# ProProject_Air001_2024-07-03.net
KiCad netlist of a schematic drawn in EasyEDA Pro
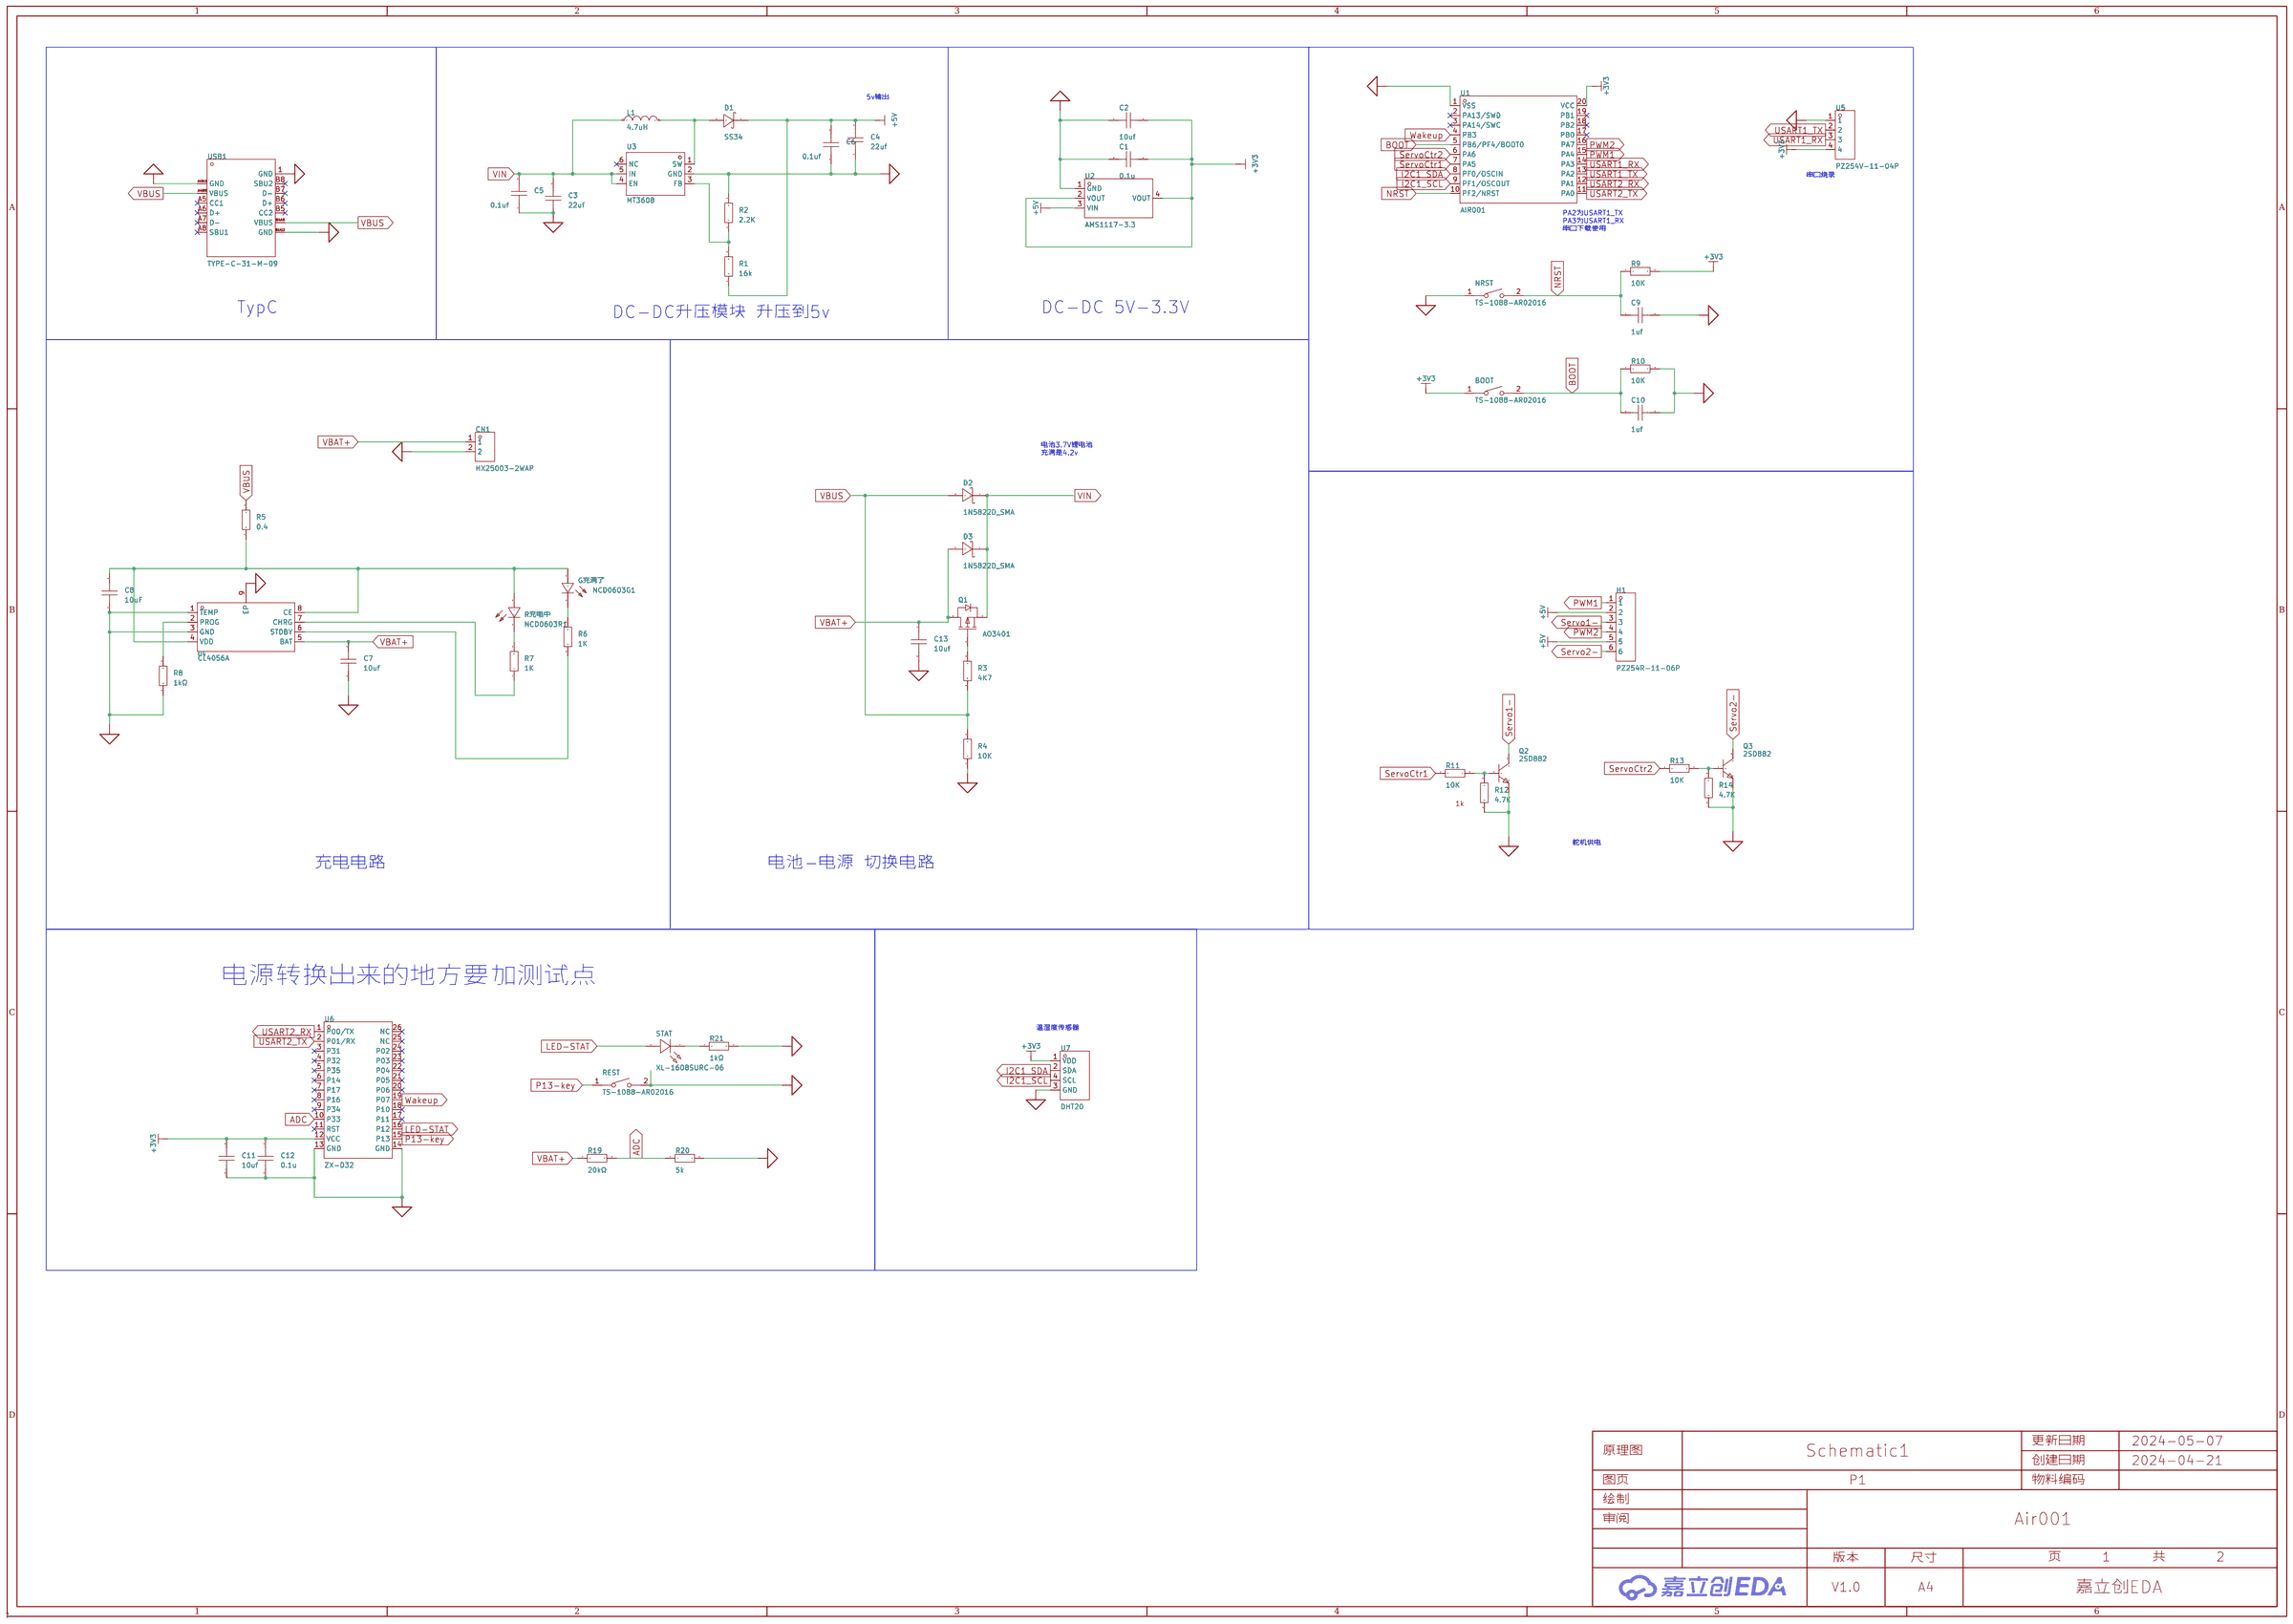
[diagram p0: schematic sheet]

(export (version "E")
  (design (tool "Eeschema 10.0.6"))
  (components
    (comp (ref "BOOT")
      (value "TS-1088-AR02016")
      (footprint "easyedapro:SW-SMD_L3.9-W3.0-P4.45")
      (fields (field (name "Manufacturer") "XUNPU(讯普)"))
      (libsource (lib "easyedapro") (part "TS-1088-AR02016"))
    )
    (comp (ref "C1")
      (value "0.1u")
      (footprint "easyedapro:C0603")
      (libsource (lib "easyedapro") (part "CapAcitance"))
    )
    (comp (ref "C2")
      (value "10uf")
      (footprint "easyedapro:C0603")
      (libsource (lib "easyedapro") (part "CapAcitance"))
    )
    (comp (ref "C3")
      (value "22uf")
      (footprint "easyedapro:C0603")
      (libsource (lib "easyedapro") (part "CapAcitance"))
    )
    (comp (ref "C4")
      (value "22uf")
      (footprint "easyedapro:C0603")
      (libsource (lib "easyedapro") (part "CapAcitance"))
    )
    (comp (ref "C5")
      (value "0.1uf")
      (footprint "easyedapro:C0603")
      (libsource (lib "easyedapro") (part "CapAcitance"))
    )
    (comp (ref "C6")
      (value "0.1uf")
      (footprint "easyedapro:C0603")
      (libsource (lib "easyedapro") (part "CapAcitance"))
    )
    (comp (ref "C7")
      (value "10uf")
      (footprint "easyedapro:C0603")
      (libsource (lib "easyedapro") (part "CapAcitance"))
    )
    (comp (ref "C8")
      (value "10uF")
      (footprint "easyedapro:C0603")
      (fields
        (field (name "Manufacturer Part") "CL10A106MA8NRNC")
        (field (name "Manufacturer") "SAMSUNG(三星)")
      )
      (libsource (lib "easyedapro") (part "CapAcitance"))
    )
    (comp (ref "C9")
      (value "1uf")
      (footprint "easyedapro:C0603")
      (libsource (lib "easyedapro") (part "CapAcitance"))
    )
    (comp (ref "C10")
      (value "1uf")
      (footprint "easyedapro:C0603")
      (libsource (lib "easyedapro") (part "CapAcitance"))
    )
    (comp (ref "C11")
      (value "10uf")
      (footprint "easyedapro:C0603")
      (libsource (lib "easyedapro") (part "CapAcitance"))
    )
    (comp (ref "C12")
      (value "0.1u")
      (footprint "easyedapro:C0603")
      (libsource (lib "easyedapro") (part "CapAcitance"))
    )
    (comp (ref "C13")
      (value "10uf")
      (footprint "easyedapro:C0603")
      (libsource (lib "easyedapro") (part "CapAcitance"))
    )
    (comp (ref "CN1")
      (value "HX25003-2WAP")
      (footprint "easyedapro:CONN-TH_2P-P2.50_HX25003-2WAP")
      (description "插针结构:1x2P;间距:2.5mm;安装方式:弯插;参考系列:XH;总PIN数:2P;排数:1;每排PIN数:2;行距:-;额定电流:-;工作温度范围:-;")
      (fields (field (name "Manufacturer") "HX(红星)"))
      (libsource (lib "easyedapro") (part "HX25003-2WAP"))
    )
    (comp (ref "D1")
      (value "SS34")
      (footprint "easyedapro:SMA_L4.3-W2.6-LS5.2-RD")
      (description "二极管配置:独立式;正向压降(Vf):550mV@3A;直流反向耐压(Vr):40V;平均整流电流(Io):3A;")
      (fields (field (name "Manufacturer") "MDD"))
      (libsource (lib "easyedapro") (part "SS34_C8678"))
    )
    (comp (ref "D2")
      (value "1N5822D_SMA")
      (footprint "easyedapro:SMA_L4.3-W2.6-LS5.2-RD")
      (description "二极管配置:独立式;正向压降(Vf):550mV@3A;直流反向耐压(Vr):40V;平均整流电流(Io):3A;")
      (fields (field (name "Manufacturer") "MDD"))
      (libsource (lib "easyedapro") (part "SS34_C8678"))
    )
    (comp (ref "D3")
      (value "1N5822D_SMA")
      (footprint "easyedapro:SMA_L4.3-W2.6-LS5.2-RD")
      (description "二极管配置:独立式;正向压降(Vf):550mV@3A;直流反向耐压(Vr):40V;平均整流电流(Io):3A;")
      (fields (field (name "Manufacturer") "MDD"))
      (libsource (lib "easyedapro") (part "SS34_C8678"))
    )
    (comp (ref "G充满了")
      (value "NCD0603G1")
      (footprint "easyedapro:LED0603-RD")
      (fields (field (name "Manufacturer") "国星光电"))
      (libsource (lib "easyedapro") (part "FC-D1608UGK-520D10"))
    )
    (comp (ref "H1")
      (value "PZ254R-11-06P")
      (footprint "easyedapro:HDR-TH_6P-P2.54-H-M-W10.4")
      (fields (field (name "Manufacturer") "XFCN(兴飞)"))
      (libsource (lib "easyedapro") (part "PZ254R-11-06P"))
    )
    (comp (ref "L1")
      (value "4.7uH")
      (fields (field (name "Manufacturer Part") "YSPI1050-4R7M") (field (name "Manufacturer") "YJYCOIN(益嘉源)"))
      (libsource (lib "easyedapro") (part "SDFL1608S100KTF"))
    )
    (comp (ref "NRST")
      (value "TS-1088-AR02016")
      (footprint "easyedapro:SW-SMD_L3.9-W3.0-P4.45")
      (fields (field (name "Manufacturer") "XUNPU(讯普)"))
      (libsource (lib "easyedapro") (part "TS-1088-AR02016"))
    )
    (comp (ref "Q1")
      (value "AO3401")
      (footprint "easyedapro:SOT-23-3_L2.9-W1.6-P1.90-LS2.8-BR")
      (fields (field (name "Manufacturer") "LGE(鲁光)"))
      (libsource (lib "easyedapro") (part "AO3401_C688915"))
    )
    (comp (ref "Q2")
      (value "2SD882")
      (footprint "easyedapro:SOT-89-3_L4.5-W2.5-P1.50-LS4.1-BR")
      (description "晶体管类型:NPN;集电极电流(Ic):3A;集射极击穿电压(Vceo):30V;功率(Pd):500mW;")
      (fields (field (name "Manufacturer") "FUXINSEMI(富芯森美)"))
      (libsource (lib "easyedapro") (part "2SD882_C842818"))
    )
    (comp (ref "Q3")
      (value "2SD882")
      (footprint "easyedapro:SOT-89-3_L4.5-W2.5-P1.50-LS4.1-BR")
      (description "晶体管类型:NPN;集电极电流(Ic):3A;集射极击穿电压(Vceo):30V;功率(Pd):500mW;")
      (fields (field (name "Manufacturer") "FUXINSEMI(富芯森美)"))
      (libsource (lib "easyedapro") (part "2SD882_C842818"))
    )
    (comp (ref "R1") (value "16k") (footprint "easyedapro:R0603") (libsource (lib "easyedapro") (part "电阻")))
    (comp (ref "R2") (value "2.2K") (footprint "easyedapro:R0603") (libsource (lib "easyedapro") (part "电阻")))
    (comp (ref "R3") (value "4K7") (footprint "easyedapro:R0603") (libsource (lib "easyedapro") (part "电阻")))
    (comp (ref "R4") (value "10K") (footprint "easyedapro:R0603") (libsource (lib "easyedapro") (part "电阻")))
    (comp (ref "R5") (value "0.4") (footprint "easyedapro:R0603") (libsource (lib "easyedapro") (part "电阻")))
    (comp (ref "R6") (value "1K") (footprint "easyedapro:R0603") (libsource (lib "easyedapro") (part "电阻")))
    (comp (ref "R7") (value "1K") (footprint "easyedapro:R0603") (libsource (lib "easyedapro") (part "电阻")))
    (comp (ref "R8")
      (value "1kΩ")
      (footprint "easyedapro:R0603")
      (fields (field (name "Manufacturer Part") "RC0603FR-071KL") (field (name "Manufacturer") "YAGEO(国巨)"))
      (libsource (lib "easyedapro") (part "电阻"))
    )
    (comp (ref "R9") (value "10K") (footprint "easyedapro:R0603") (libsource (lib "easyedapro") (part "电阻")))
    (comp (ref "R10") (value "10K") (footprint "easyedapro:R0603") (libsource (lib "easyedapro") (part "电阻")))
    (comp (ref "R11") (value "10K") (footprint "easyedapro:R0603") (libsource (lib "easyedapro") (part "电阻")))
    (comp (ref "R12")
      (value "4.7K")
      (footprint "easyedapro:R0603")
      (libsource (lib "easyedapro") (part "电阻"))
    )
    (comp (ref "R13") (value "10K") (footprint "easyedapro:R0603") (libsource (lib "easyedapro") (part "电阻")))
    (comp (ref "R14")
      (value "4.7K")
      (footprint "easyedapro:R0603")
      (libsource (lib "easyedapro") (part "电阻"))
    )
    (comp (ref "R19")
      (value "20kΩ")
      (fields
        (field (name "Manufacturer Part") "0603WAF1002T5E")
        (field (name "Manufacturer") "UNI-ROYAL(厚声)")
      )
      (libsource (lib "easyedapro") (part "电阻"))
    )
    (comp (ref "R20")
      (value "5k")
      (fields
        (field (name "Manufacturer Part") "0603WAF2701T5E")
        (field (name "Manufacturer") "UNI-ROYAL(厚声)")
      )
      (libsource (lib "easyedapro") (part "电阻"))
    )
    (comp (ref "R21")
      (value "1kΩ")
      (fields (field (name "Manufacturer Part") "RC0603FR-071KL") (field (name "Manufacturer") "YAGEO(国巨)"))
      (libsource (lib "easyedapro") (part "电阻"))
    )
    (comp (ref "REST")
      (value "TS-1088-AR02016")
      (footprint "easyedapro:SW-SMD_L3.9-W3.0-P4.45")
      (fields (field (name "Manufacturer") "XUNPU(讯普)"))
      (libsource (lib "easyedapro") (part "TS-1088-AR02016"))
    )
    (comp (ref "R充电中")
      (value "NCD0603R1")
      (footprint "easyedapro:LED0603-RD_RED")
      (fields (field (name "Manufacturer") "国星光电"))
      (libsource (lib "easyedapro") (part "FC-DA1608HRK-620D"))
    )
    (comp (ref "STAT")
      (value "XL-1608SURC-06")
      (footprint "easyedapro:LED0603-RD_RED")
      (description "发光颜色:红色;功率:55mW;正向电流:25mA;主波长:617nm~621nm;透镜颜色:无色透明透镜;色温:-;发光角度:120°;载带方式:正贴;工作温度:-30°C~+85°C;")
      (fields (field (name "Manufacturer") "XINGLIGHT(成兴光)"))
      (libsource (lib "easyedapro") (part "XL-1608SURC-06"))
    )
    (comp (ref "U1")
      (value "AIR001")
      (footprint "easyedapro:TSSOP-20_L6.5-W4.4-P0.65-LS6.4-BL")
      (libsource (lib "easyedapro") (part "AIR001"))
    )
    (comp (ref "U2")
      (value "AMS1117-3.3")
      (footprint "easyedapro:SOT-223-3_L6.5-W3.4-P2.30-LS7.0-BR")
      (description "输出类型:固定;最大输入电压:-;输出电压:3.3V;最大输出电流:1A;电源纹波抑制比(PSRR):72dB@(120Hz);输出极性:正极;")
      (fields (field (name "Manufacturer") "AMS"))
      (libsource (lib "easyedapro") (part "AMS1117-3.3"))
    )
    (comp (ref "U3")
      (value "MT3608")
      (footprint "easyedapro:SOT-23-6_L2.9-W1.6-P0.95-LS2.8-BL")
      (description "功能类型:升压型;输入电压:2V~24V;输出电压:28V;输出电流(最大值):-;")
      (fields (field (name "Manufacturer") "西安航天民芯"))
      (libsource (lib "easyedapro") (part "MT3608"))
    )
    (comp (ref "U4")
      (value "CL4056A")
      (footprint "easyedapro:ESOP-8_L4.9-W3.9-P1.27-LS6.0-BL-EP")
      (fields (field (name "Manufacturer") "CHIPLINK(芯联)"))
      (libsource (lib "easyedapro") (part "CL4056"))
    )
    (comp (ref "U5")
      (value "PZ254V-11-04P")
      (footprint "easyedapro:HDR-TH_4P-P2.54-V-M-3")
      (fields (field (name "Manufacturer") "XFCN(兴飞)"))
      (libsource (lib "easyedapro") (part "SIP4-CON4排针"))
    )
    (comp (ref "U6")
      (value "ZX-D32")
      (footprint "easyedapro:WIFIM-SMD_26P-L26.7-W13.0-P1.50")
      (libsource (lib "easyedapro") (part "ZX-D32_C9900104345"))
    )
    (comp (ref "U7")
      (value "DHT20")
      (footprint "easyedapro:SENSOR-TH_DHT20")
      (fields (field (name "Manufacturer") "广州奥松"))
      (libsource (lib "easyedapro") (part "DHT20"))
    )
    (comp (ref "USB1")
      (value "TYPE-C-31-M-09")
      (footprint "easyedapro:USB-C-SMD_TYPE-C-31-M-09")
      (description "连接器类型:Type-C;标准:-;公母:母;端口数量:1;触点数量:16P;安装方式:卧贴;额定电流 - 电源:-;工作温度范围:-40°C~+80°C;")
      (fields (field (name "Manufacturer") "韩国韩荣"))
      (libsource (lib "easyedapro") (part "TYPE-C-31-M-09"))
    )
  )
  (nets
    (net (code "1") (name "+3V3") (class "Default")
      (node (ref "BOOT") (pin "1") (pinfunction "1_1") (pintype "unspecified"))
      (node (ref "C1") (pin "1") (pinfunction "1_1") (pintype "input"))
      (node (ref "C11") (pin "2") (pinfunction "2_2") (pintype "input"))
      (node (ref "C12") (pin "1") (pinfunction "1_1") (pintype "input"))
      (node (ref "C2") (pin "2") (pinfunction "2_2") (pintype "input"))
      (node (ref "R9") (pin "2") (pinfunction "2_2") (pintype "input"))
      (node (ref "U1") (pin "20") (pinfunction "VCC_20") (pintype "unspecified"))
      (node (ref "U2") (pin "2") (pinfunction "VOUT_2") (pintype "unspecified"))
      (node (ref "U2") (pin "4") (pinfunction "VOUT_4") (pintype "unspecified"))
      (node (ref "U5") (pin "4") (pinfunction "4_4") (pintype "unspecified"))
      (node (ref "U6") (pin "12") (pinfunction "VCC_12") (pintype "unspecified"))
      (node (ref "U7") (pin "1") (pinfunction "VDD_1") (pintype "unspecified"))
    )
    (net (code "2") (name "+5V") (class "Default")
      (node (ref "C4") (pin "2") (pinfunction "2_2") (pintype "input"))
      (node (ref "C6") (pin "2") (pinfunction "2_2") (pintype "input"))
      (node (ref "D1") (pin "1") (pinfunction "K_1") (pintype "unspecified"))
      (node (ref "H1") (pin "2") (pinfunction "2_2") (pintype "unspecified"))
      (node (ref "H1") (pin "5") (pinfunction "5_5") (pintype "unspecified"))
      (node (ref "R1") (pin "1") (pinfunction "1_1") (pintype "input"))
      (node (ref "U2") (pin "3") (pinfunction "VIN_3") (pintype "unspecified"))
    )
    (net (code "3") (name "ADC") (class "Default")
      (node (ref "R19") (pin "2") (pinfunction "2_2") (pintype "input"))
      (node (ref "R20") (pin "1") (pinfunction "1_1") (pintype "input"))
      (node (ref "U6") (pin "10") (pinfunction "P33_10") (pintype "unspecified"))
    )
    (net (code "4") (name "AGND") (class "Default")
      (node (ref "C1") (pin "2") (pinfunction "2_2") (pintype "input"))
      (node (ref "C10") (pin "2") (pinfunction "2_2") (pintype "input"))
      (node (ref "C11") (pin "1") (pinfunction "1_1") (pintype "input"))
      (node (ref "C12") (pin "2") (pinfunction "2_2") (pintype "input"))
      (node (ref "C13") (pin "2") (pinfunction "2_2") (pintype "input"))
      (node (ref "C2") (pin "1") (pinfunction "1_1") (pintype "input"))
      (node (ref "C3") (pin "1") (pinfunction "1_1") (pintype "input"))
      (node (ref "C4") (pin "1") (pinfunction "1_1") (pintype "input"))
      (node (ref "C5") (pin "1") (pinfunction "1_1") (pintype "input"))
      (node (ref "C6") (pin "1") (pinfunction "1_1") (pintype "input"))
      (node (ref "C7") (pin "2") (pinfunction "2_2") (pintype "input"))
      (node (ref "C8") (pin "1") (pinfunction "1_1") (pintype "input"))
      (node (ref "C9") (pin "2") (pinfunction "2_2") (pintype "input"))
      (node (ref "CN1") (pin "2") (pinfunction "2_2") (pintype "unspecified"))
      (node (ref "NRST") (pin "1") (pinfunction "1_1") (pintype "unspecified"))
      (node (ref "Q2") (pin "3") (pinfunction "E_3") (pintype "unspecified"))
      (node (ref "Q3") (pin "3") (pinfunction "E_3") (pintype "unspecified"))
      (node (ref "R10") (pin "2") (pinfunction "2_2") (pintype "input"))
      (node (ref "R12") (pin "1") (pinfunction "1_1") (pintype "input"))
      (node (ref "R14") (pin "1") (pinfunction "1_1") (pintype "input"))
      (node (ref "R2") (pin "2") (pinfunction "2_2") (pintype "input"))
      (node (ref "R20") (pin "2") (pinfunction "2_2") (pintype "input"))
      (node (ref "R21") (pin "2") (pinfunction "2_2") (pintype "input"))
      (node (ref "R4") (pin "1") (pinfunction "1_1") (pintype "input"))
      (node (ref "R8") (pin "1") (pinfunction "1_1") (pintype "input"))
      (node (ref "REST") (pin "2") (pinfunction "2_2") (pintype "unspecified"))
      (node (ref "U1") (pin "1") (pinfunction "VSS_1") (pintype "unspecified"))
      (node (ref "U2") (pin "1") (pinfunction "GND_1") (pintype "unspecified"))
      (node (ref "U3") (pin "2") (pinfunction "GND_2") (pintype "input"))
      (node (ref "U4") (pin "1") (pinfunction "TEMP_1") (pintype "input"))
      (node (ref "U4") (pin "3") (pinfunction "GND_3") (pintype "input"))
      (node (ref "U4") (pin "9") (pinfunction "EP_9") (pintype "input"))
      (node (ref "U5") (pin "1") (pinfunction "1_1") (pintype "unspecified"))
      (node (ref "U6") (pin "13") (pinfunction "GND_13") (pintype "unspecified"))
      (node (ref "U6") (pin "14") (pinfunction "GND_14") (pintype "unspecified"))
      (node (ref "U7") (pin "3") (pinfunction "GND_3") (pintype "unspecified"))
      (node (ref "USB1") (pin "1") (pinfunction "GND_1") (pintype "unspecified"))
      (node (ref "USB1") (pin "A1B12") (pinfunction "GND_A1B12") (pintype "unspecified"))
      (node (ref "USB1") (pin "B1A12") (pinfunction "GND_B1A12") (pintype "unspecified"))
    )
    (net (code "5") (name "BOOT") (class "Default")
      (node (ref "BOOT") (pin "2") (pinfunction "2_2") (pintype "unspecified"))
      (node (ref "C10") (pin "1") (pinfunction "1_1") (pintype "input"))
      (node (ref "R10") (pin "1") (pinfunction "1_1") (pintype "input"))
      (node (ref "U1") (pin "5") (pinfunction "PB6/PF4/BOOT0_5") (pintype "unspecified"))
    )
    (net (code "6") (name "I2C1_SCL") (class "Default")
      (node (ref "U1") (pin "9") (pinfunction "PF1/OSCOUT_9") (pintype "unspecified"))
      (node (ref "U7") (pin "4") (pinfunction "SCL_4") (pintype "unspecified"))
    )
    (net (code "7") (name "I2C1_SDA") (class "Default")
      (node (ref "U1") (pin "8") (pinfunction "PF0/OSCIN_8") (pintype "unspecified"))
      (node (ref "U7") (pin "2") (pinfunction "SDA_2") (pintype "unspecified"))
    )
    (net (code "8") (name "LED-STAT") (class "Default")
      (node (ref "STAT") (pin "2") (pinfunction "A_2") (pintype "unspecified"))
      (node (ref "U6") (pin "16") (pinfunction "P12_16") (pintype "unspecified"))
    )
    (net (code "9") (name "NRST") (class "Default")
      (node (ref "C9") (pin "1") (pinfunction "1_1") (pintype "input"))
      (node (ref "NRST") (pin "2") (pinfunction "2_2") (pintype "unspecified"))
      (node (ref "R9") (pin "1") (pinfunction "1_1") (pintype "input"))
      (node (ref "U1") (pin "10") (pinfunction "PF2/NRST_10") (pintype "unspecified"))
    )
    (net (code "10") (name "Net-(D1-A)") (class "Default")
      (node (ref "D1") (pin "2") (pinfunction "A_2") (pintype "unspecified"))
      (node (ref "L1") (pin "2") (pinfunction "2_2") (pintype "unspecified"))
      (node (ref "U3") (pin "1") (pinfunction "SW_1") (pintype "input"))
    )
    (net (code "11") (name "Net-(G充满了-A)") (class "Default")
      (node (ref "C8") (pin "2") (pinfunction "2_2") (pintype "input"))
      (node (ref "G充满了") (pin "2") (pinfunction "A_2") (pintype "input"))
      (node (ref "R5") (pin "1") (pinfunction "1_1") (pintype "input"))
      (node (ref "R充电中") (pin "2") (pinfunction "A_2") (pintype "input"))
      (node (ref "U4") (pin "4") (pinfunction "VDD_4") (pintype "input"))
      (node (ref "U4") (pin "8") (pinfunction "CE_8") (pintype "input"))
    )
    (net (code "12") (name "Net-(G充满了-K)") (class "Default")
      (node (ref "G充满了") (pin "1") (pinfunction "K_1") (pintype "input"))
      (node (ref "R6") (pin "2") (pinfunction "2_2") (pintype "input"))
    )
    (net (code "13") (name "Net-(Q1-G)") (class "Default")
      (node (ref "Q1") (pin "1") (pinfunction "G_1") (pintype "unspecified"))
      (node (ref "R3") (pin "2") (pinfunction "2_2") (pintype "input"))
    )
    (net (code "14") (name "Net-(Q2-B)") (class "Default")
      (node (ref "Q2") (pin "1") (pinfunction "B_1") (pintype "unspecified"))
      (node (ref "R11") (pin "2") (pinfunction "2_2") (pintype "input"))
      (node (ref "R12") (pin "2") (pinfunction "2_2") (pintype "input"))
    )
    (net (code "15") (name "Net-(Q3-B)") (class "Default")
      (node (ref "Q3") (pin "1") (pinfunction "B_1") (pintype "unspecified"))
      (node (ref "R13") (pin "2") (pinfunction "2_2") (pintype "input"))
      (node (ref "R14") (pin "2") (pinfunction "2_2") (pintype "input"))
    )
    (net (code "16") (name "Net-(R充电中-K)") (class "Default")
      (node (ref "R7") (pin "2") (pinfunction "2_2") (pintype "input"))
      (node (ref "R充电中") (pin "1") (pinfunction "K_1") (pintype "input"))
    )
    (net (code "17") (name "Net-(STAT-K)") (class "Default")
      (node (ref "R21") (pin "1") (pinfunction "1_1") (pintype "input"))
      (node (ref "STAT") (pin "1") (pinfunction "K_1") (pintype "unspecified"))
    )
    (net (code "18") (name "Net-(U3-FB)") (class "Default")
      (node (ref "R1") (pin "2") (pinfunction "2_2") (pintype "input"))
      (node (ref "R2") (pin "1") (pinfunction "1_1") (pintype "input"))
      (node (ref "U3") (pin "3") (pinfunction "FB_3") (pintype "input"))
    )
    (net (code "19") (name "Net-(U4-CHRG)") (class "Default")
      (node (ref "R7") (pin "1") (pinfunction "1_1") (pintype "input"))
      (node (ref "U4") (pin "7") (pinfunction "CHRG_7") (pintype "input"))
    )
    (net (code "20") (name "Net-(U4-PROG)") (class "Default")
      (node (ref "R8") (pin "2") (pinfunction "2_2") (pintype "input"))
      (node (ref "U4") (pin "2") (pinfunction "PROG_2") (pintype "input"))
    )
    (net (code "21") (name "Net-(U4-STDBY)") (class "Default")
      (node (ref "R6") (pin "1") (pinfunction "1_1") (pintype "input"))
      (node (ref "U4") (pin "6") (pinfunction "STDBY_6") (pintype "input"))
    )
    (net (code "22") (name "P13-key") (class "Default")
      (node (ref "REST") (pin "1") (pinfunction "1_1") (pintype "unspecified"))
      (node (ref "U6") (pin "15") (pinfunction "P13_15") (pintype "unspecified"))
    )
    (net (code "23") (name "PWM1") (class "Default")
      (node (ref "H1") (pin "1") (pinfunction "1_1") (pintype "unspecified"))
      (node (ref "U1") (pin "15") (pinfunction "PA4_15") (pintype "unspecified"))
    )
    (net (code "24") (name "PWM2") (class "Default")
      (node (ref "H1") (pin "4") (pinfunction "4_4") (pintype "unspecified"))
      (node (ref "U1") (pin "16") (pinfunction "PA7_16") (pintype "unspecified"))
    )
    (net (code "25") (name "Servo1-") (class "Default")
      (node (ref "H1") (pin "3") (pinfunction "3_3") (pintype "unspecified"))
      (node (ref "Q2") (pin "2") (pinfunction "C_2") (pintype "unspecified"))
    )
    (net (code "26") (name "Servo2-") (class "Default")
      (node (ref "H1") (pin "6") (pinfunction "6_6") (pintype "unspecified"))
      (node (ref "Q3") (pin "2") (pinfunction "C_2") (pintype "unspecified"))
    )
    (net (code "27") (name "ServoCtr1") (class "Default")
      (node (ref "R11") (pin "1") (pinfunction "1_1") (pintype "input"))
      (node (ref "U1") (pin "7") (pinfunction "PA5_7") (pintype "unspecified"))
    )
    (net (code "28") (name "ServoCtr2") (class "Default")
      (node (ref "R13") (pin "1") (pinfunction "1_1") (pintype "input"))
      (node (ref "U1") (pin "6") (pinfunction "PA6_6") (pintype "unspecified"))
    )
    (net (code "29") (name "USART1_RX") (class "Default")
      (node (ref "U1") (pin "14") (pinfunction "PA3_14") (pintype "unspecified"))
      (node (ref "U5") (pin "3") (pinfunction "3_3") (pintype "unspecified"))
    )
    (net (code "30") (name "USART1_TX") (class "Default")
      (node (ref "U1") (pin "13") (pinfunction "PA2_13") (pintype "unspecified"))
      (node (ref "U5") (pin "2") (pinfunction "2_2") (pintype "unspecified"))
    )
    (net (code "31") (name "USART2_RX") (class "Default")
      (node (ref "U1") (pin "12") (pinfunction "PA1_12") (pintype "unspecified"))
      (node (ref "U6") (pin "1") (pinfunction "P00/TX_1") (pintype "unspecified"))
    )
    (net (code "32") (name "USART2_TX") (class "Default")
      (node (ref "U1") (pin "11") (pinfunction "PA0_11") (pintype "unspecified"))
      (node (ref "U6") (pin "2") (pinfunction "P01/RX_2") (pintype "unspecified"))
    )
    (net (code "33") (name "VBAT+") (class "Default")
      (node (ref "C13") (pin "1") (pinfunction "1_1") (pintype "input"))
      (node (ref "C7") (pin "1") (pinfunction "1_1") (pintype "input"))
      (node (ref "CN1") (pin "1") (pinfunction "1_1") (pintype "unspecified"))
      (node (ref "D3") (pin "2") (pinfunction "A_2") (pintype "unspecified"))
      (node (ref "Q1") (pin "3") (pinfunction "D_3") (pintype "unspecified"))
      (node (ref "R19") (pin "1") (pinfunction "1_1") (pintype "input"))
      (node (ref "U4") (pin "5") (pinfunction "BAT_5") (pintype "input"))
    )
    (net (code "34") (name "VBUS") (class "Default")
      (node (ref "D2") (pin "2") (pinfunction "A_2") (pintype "unspecified"))
      (node (ref "R3") (pin "1") (pinfunction "1_1") (pintype "input"))
      (node (ref "R4") (pin "2") (pinfunction "2_2") (pintype "input"))
      (node (ref "R5") (pin "2") (pinfunction "2_2") (pintype "input"))
      (node (ref "USB1") (pin "A4B9") (pinfunction "VBUS_A4B9") (pintype "unspecified"))
      (node (ref "USB1") (pin "B4A9") (pinfunction "VBUS_B4A9") (pintype "unspecified"))
    )
    (net (code "35") (name "VIN") (class "Default")
      (node (ref "C3") (pin "2") (pinfunction "2_2") (pintype "input"))
      (node (ref "C5") (pin "2") (pinfunction "2_2") (pintype "input"))
      (node (ref "D2") (pin "1") (pinfunction "K_1") (pintype "unspecified"))
      (node (ref "D3") (pin "1") (pinfunction "K_1") (pintype "unspecified"))
      (node (ref "L1") (pin "1") (pinfunction "1_1") (pintype "unspecified"))
      (node (ref "Q1") (pin "2") (pinfunction "S_2") (pintype "unspecified"))
      (node (ref "U3") (pin "4") (pinfunction "EN_4") (pintype "input"))
      (node (ref "U3") (pin "5") (pinfunction "IN_5") (pintype "input"))
    )
    (net (code "36") (name "Wakeup") (class "Default")
      (node (ref "U1") (pin "4") (pinfunction "PB3_4") (pintype "unspecified"))
      (node (ref "U6") (pin "19") (pinfunction "P07_19") (pintype "unspecified"))
    )
    (net (code "37") (name "unconnected-(U1-PA13{slash}SWD-Pad2)") (class "Default")
      (node (ref "U1") (pin "2") (pinfunction "PA13/SWD_2") (pintype "unspecified+no_connect"))
    )
    (net (code "38") (name "unconnected-(U1-PA14{slash}SWC-Pad3)") (class "Default")
      (node (ref "U1") (pin "3") (pinfunction "PA14/SWC_3") (pintype "unspecified+no_connect"))
    )
    (net (code "39") (name "unconnected-(U1-PB0-Pad17)") (class "Default")
      (node (ref "U1") (pin "17") (pinfunction "PB0_17") (pintype "unspecified+no_connect"))
    )
    (net (code "40") (name "unconnected-(U1-PB1-Pad19)") (class "Default")
      (node (ref "U1") (pin "19") (pinfunction "PB1_19") (pintype "unspecified+no_connect"))
    )
    (net (code "41") (name "unconnected-(U1-PB2-Pad18)") (class "Default")
      (node (ref "U1") (pin "18") (pinfunction "PB2_18") (pintype "unspecified+no_connect"))
    )
    (net (code "42") (name "unconnected-(U3-NC-Pad6)") (class "Default")
      (node (ref "U3") (pin "6") (pinfunction "NC_6") (pintype "input+no_connect"))
    )
    (net (code "43") (name "unconnected-(U6-NC-Pad25)") (class "Default")
      (node (ref "U6") (pin "25") (pinfunction "NC_25") (pintype "unspecified+no_connect"))
    )
    (net (code "44") (name "unconnected-(U6-NC-Pad26)") (class "Default")
      (node (ref "U6") (pin "26") (pinfunction "NC_26") (pintype "unspecified+no_connect"))
    )
    (net (code "45") (name "unconnected-(U6-P02-Pad24)") (class "Default")
      (node (ref "U6") (pin "24") (pinfunction "P02_24") (pintype "unspecified+no_connect"))
    )
    (net (code "46") (name "unconnected-(U6-P03-Pad23)") (class "Default")
      (node (ref "U6") (pin "23") (pinfunction "P03_23") (pintype "unspecified+no_connect"))
    )
    (net (code "47") (name "unconnected-(U6-P04-Pad22)") (class "Default")
      (node (ref "U6") (pin "22") (pinfunction "P04_22") (pintype "unspecified+no_connect"))
    )
    (net (code "48") (name "unconnected-(U6-P05-Pad21)") (class "Default")
      (node (ref "U6") (pin "21") (pinfunction "P05_21") (pintype "unspecified+no_connect"))
    )
    (net (code "49") (name "unconnected-(U6-P06-Pad20)") (class "Default")
      (node (ref "U6") (pin "20") (pinfunction "P06_20") (pintype "unspecified+no_connect"))
    )
    (net (code "50") (name "unconnected-(U6-P10-Pad18)") (class "Default")
      (node (ref "U6") (pin "18") (pinfunction "P10_18") (pintype "unspecified+no_connect"))
    )
    (net (code "51") (name "unconnected-(U6-P11-Pad17)") (class "Default")
      (node (ref "U6") (pin "17") (pinfunction "P11_17") (pintype "unspecified+no_connect"))
    )
    (net (code "52") (name "unconnected-(U6-P14-Pad6)") (class "Default")
      (node (ref "U6") (pin "6") (pinfunction "P14_6") (pintype "unspecified+no_connect"))
    )
    (net (code "53") (name "unconnected-(U6-P16-Pad8)") (class "Default")
      (node (ref "U6") (pin "8") (pinfunction "P16_8") (pintype "unspecified+no_connect"))
    )
    (net (code "54") (name "unconnected-(U6-P17-Pad7)") (class "Default")
      (node (ref "U6") (pin "7") (pinfunction "P17_7") (pintype "unspecified+no_connect"))
    )
    (net (code "55") (name "unconnected-(U6-P31-Pad3)") (class "Default")
      (node (ref "U6") (pin "3") (pinfunction "P31_3") (pintype "unspecified+no_connect"))
    )
    (net (code "56") (name "unconnected-(U6-P32-Pad4)") (class "Default")
      (node (ref "U6") (pin "4") (pinfunction "P32_4") (pintype "unspecified+no_connect"))
    )
    (net (code "57") (name "unconnected-(U6-P34-Pad9)") (class "Default")
      (node (ref "U6") (pin "9") (pinfunction "P34_9") (pintype "unspecified+no_connect"))
    )
    (net (code "58") (name "unconnected-(U6-P35-Pad5)") (class "Default")
      (node (ref "U6") (pin "5") (pinfunction "P35_5") (pintype "unspecified+no_connect"))
    )
    (net (code "59") (name "unconnected-(U6-RST-Pad11)") (class "Default")
      (node (ref "U6") (pin "11") (pinfunction "RST_11") (pintype "unspecified+no_connect"))
    )
    (net (code "60") (name "unconnected-(USB1-CC1-PadA5)") (class "Default")
      (node (ref "USB1") (pin "A5") (pinfunction "CC1_A5") (pintype "unspecified+no_connect"))
    )
    (net (code "61") (name "unconnected-(USB1-CC2-PadB5)") (class "Default")
      (node (ref "USB1") (pin "B5") (pinfunction "CC2_B5") (pintype "unspecified+no_connect"))
    )
    (net (code "62") (name "unconnected-(USB1-D+-PadA6)") (class "Default")
      (node (ref "USB1") (pin "A6") (pinfunction "D+_A6") (pintype "unspecified+no_connect"))
    )
    (net (code "63") (name "unconnected-(USB1-D+-PadB6)") (class "Default")
      (node (ref "USB1") (pin "B6") (pinfunction "D+_B6") (pintype "unspecified+no_connect"))
    )
    (net (code "64") (name "unconnected-(USB1-D--PadA7)") (class "Default")
      (node (ref "USB1") (pin "A7") (pinfunction "D-_A7") (pintype "unspecified+no_connect"))
    )
    (net (code "65") (name "unconnected-(USB1-D--PadB7)") (class "Default")
      (node (ref "USB1") (pin "B7") (pinfunction "D-_B7") (pintype "unspecified+no_connect"))
    )
    (net (code "66") (name "unconnected-(USB1-SBU1-PadA8)") (class "Default")
      (node (ref "USB1") (pin "A8") (pinfunction "SBU1_A8") (pintype "unspecified+no_connect"))
    )
    (net (code "67") (name "unconnected-(USB1-SBU2-PadB8)") (class "Default")
      (node (ref "USB1") (pin "B8") (pinfunction "SBU2_B8") (pintype "unspecified+no_connect"))
    )
  )
)
